# n64cart-v2-soic-8.net
KiCad netlist of a schematic drawn in EAGLE
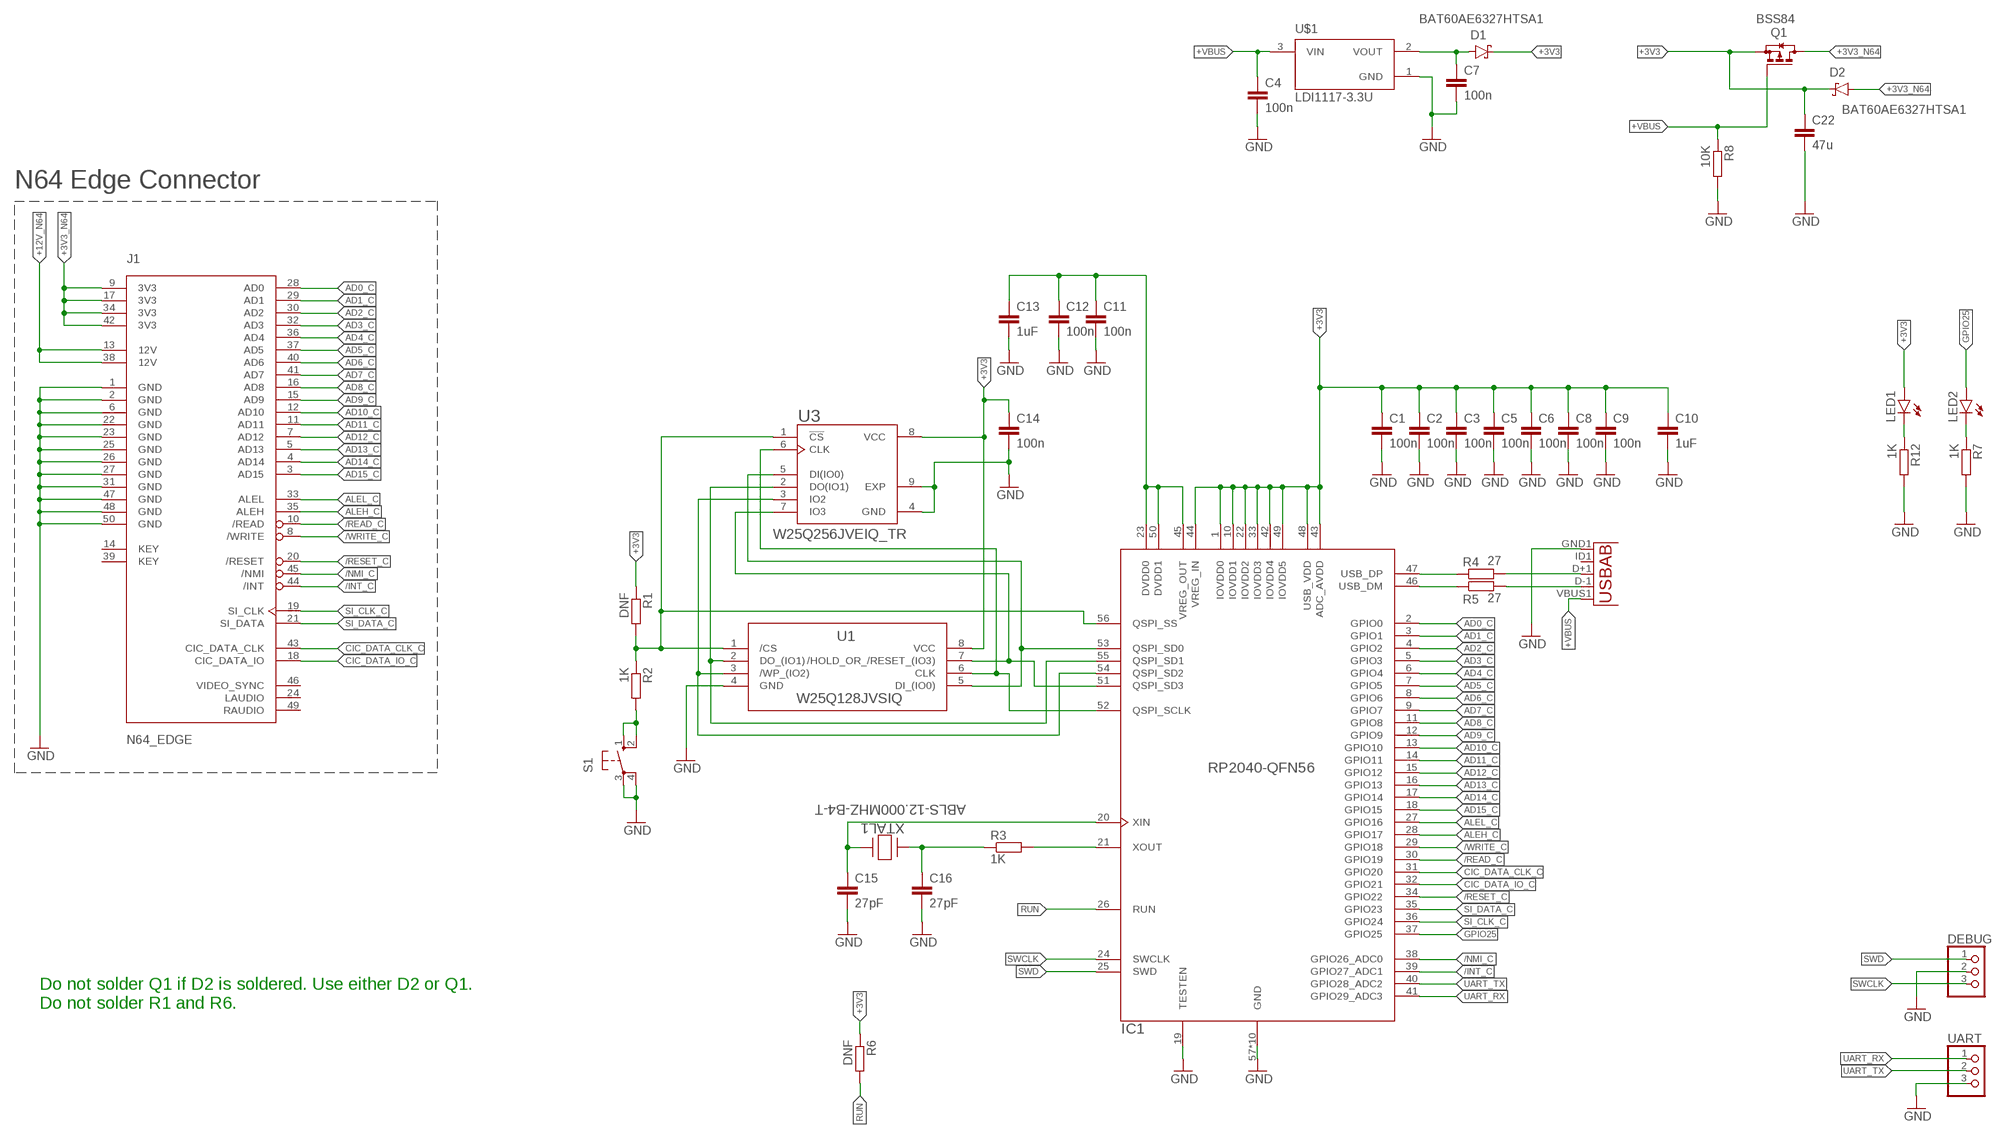
[diagram p0: schematic, sheet 1]

(export (version "E")
  (design (tool "Eeschema 10.0.6"))
  (components
    (comp (ref "C1")
      (value "100n")
      (footprint "eagle-import:C0402")
      (libsource (lib "eagle-import") (part "C-EUC0402"))
    )
    (comp (ref "C2")
      (value "100n")
      (footprint "eagle-import:C0402")
      (libsource (lib "eagle-import") (part "C-EUC0402"))
    )
    (comp (ref "C3")
      (value "100n")
      (footprint "eagle-import:C0402")
      (libsource (lib "eagle-import") (part "C-EUC0402"))
    )
    (comp (ref "C4")
      (value "100n")
      (footprint "eagle-import:C0402")
      (libsource (lib "eagle-import") (part "C-EUC0402"))
    )
    (comp (ref "C5")
      (value "100n")
      (footprint "eagle-import:C0402")
      (libsource (lib "eagle-import") (part "C-EUC0402"))
    )
    (comp (ref "C6")
      (value "100n")
      (footprint "eagle-import:C0402")
      (libsource (lib "eagle-import") (part "C-EUC0402"))
    )
    (comp (ref "C7")
      (value "100n")
      (footprint "eagle-import:C0402")
      (libsource (lib "eagle-import") (part "C-EUC0402"))
    )
    (comp (ref "C8")
      (value "100n")
      (footprint "eagle-import:C0402")
      (libsource (lib "eagle-import") (part "C-EUC0402"))
    )
    (comp (ref "C9")
      (value "100n")
      (footprint "eagle-import:C0402")
      (libsource (lib "eagle-import") (part "C-EUC0402"))
    )
    (comp (ref "C10")
      (value "1uF")
      (footprint "eagle-import:C0402")
      (libsource (lib "eagle-import") (part "C-EUC0402"))
    )
    (comp (ref "C11")
      (value "100n")
      (footprint "eagle-import:C0402")
      (libsource (lib "eagle-import") (part "C-EUC0402"))
    )
    (comp (ref "C12")
      (value "100n")
      (footprint "eagle-import:C0402")
      (libsource (lib "eagle-import") (part "C-EUC0402"))
    )
    (comp (ref "C13")
      (value "1uF")
      (footprint "eagle-import:C0402")
      (libsource (lib "eagle-import") (part "C-EUC0402"))
    )
    (comp (ref "C14")
      (value "100n")
      (footprint "eagle-import:C0402")
      (libsource (lib "eagle-import") (part "C-EUC0402"))
    )
    (comp (ref "C15")
      (value "27pF")
      (footprint "eagle-import:C0402")
      (libsource (lib "eagle-import") (part "C-EUC0402"))
    )
    (comp (ref "C16")
      (value "27pF")
      (footprint "eagle-import:C0402")
      (libsource (lib "eagle-import") (part "C-EUC0402"))
    )
    (comp (ref "C22")
      (value "47u")
      (footprint "eagle-import:C0805")
      (libsource (lib "eagle-import") (part "C-EUC0805"))
    )
    (comp (ref "D1")
      (value "BAT60AE6327HTSA1")
      (footprint "eagle-import:SOD323_ST")
      (libsource (lib "eagle-import") (part "BAT60J"))
    )
    (comp (ref "D2")
      (value "BAT60AE6327HTSA1")
      (footprint "eagle-import:SOD323_ST")
      (libsource (lib "eagle-import") (part "BAT60J"))
    )
    (comp (ref "DEBUG")
      (value "PINHD-1X3")
      (footprint "eagle-import:1X03")
      (libsource (lib "eagle-import") (part "PINHD-1X3"))
    )
    (comp (ref "IC1")
      (value "RP2040-QFN56")
      (footprint "eagle-import:RP2040-QFN-56")
      (libsource (lib "eagle-import") (part "RP2040-QFN56"))
    )
    (comp (ref "J1")
      (value "N64_EDGE")
      (footprint "eagle-import:N64_EDGE")
      (libsource (lib "eagle-import") (part "N64_EDGE"))
    )
    (comp (ref "LED1")
      (value "LED5MM")
      (footprint "eagle-import:LED5MM")
      (libsource (lib "eagle-import") (part "LED5MM"))
    )
    (comp (ref "LED2")
      (value "LED5MM")
      (footprint "eagle-import:LED5MM")
      (libsource (lib "eagle-import") (part "LED5MM"))
    )
    (comp (ref "Q1")
      (value "BSS84")
      (footprint "eagle-import:SOT23")
      (libsource (lib "eagle-import") (part "BSS84"))
    )
    (comp (ref "R1")
      (value "DNF")
      (footprint "eagle-import:R0402")
      (libsource (lib "eagle-import") (part "R-EU_R0402"))
    )
    (comp (ref "R2")
      (value "1K")
      (footprint "eagle-import:R0402")
      (libsource (lib "eagle-import") (part "R-EU_R0402"))
    )
    (comp (ref "R3")
      (value "1K")
      (footprint "eagle-import:R0402")
      (libsource (lib "eagle-import") (part "R-EU_R0402"))
    )
    (comp (ref "R4")
      (value "27")
      (footprint "eagle-import:R0402")
      (libsource (lib "eagle-import") (part "R-EU_R0402"))
    )
    (comp (ref "R5")
      (value "27")
      (footprint "eagle-import:R0402")
      (libsource (lib "eagle-import") (part "R-EU_R0402"))
    )
    (comp (ref "R6")
      (value "DNF")
      (footprint "eagle-import:R0402")
      (libsource (lib "eagle-import") (part "R-EU_R0402"))
    )
    (comp (ref "R7")
      (value "1K")
      (footprint "eagle-import:R0402")
      (libsource (lib "eagle-import") (part "R-EU_R0402"))
    )
    (comp (ref "R8")
      (value "10K")
      (footprint "eagle-import:R0402")
      (libsource (lib "eagle-import") (part "R-EU_R0402"))
    )
    (comp (ref "R12")
      (value "1K")
      (footprint "eagle-import:R0402")
      (libsource (lib "eagle-import") (part "R-EU_R0402"))
    )
    (comp (ref "S1")
      (value "10-XX")
      (footprint "eagle-import:B3F-10XX")
      (fields (field (name "MPN") "B3F-1000"))
      (libsource (lib "eagle-import") (part "10-XX"))
    )
    (comp (ref "U$1")
      (value "LDI1117-3.3U")
      (footprint "eagle-import:LDI1117-3.3U")
      (libsource (lib "eagle-import") (part "LDI1117-3.3U"))
    )
    (comp (ref "U1")
      (value "W25Q128JVSIQ")
      (footprint "eagle-import:SOIC_128JVSIQ_WIN")
      (fields (field (name "COPYRIGHT") "Copyright (C) 2022 Ultra Librarian. All rights reserved."))
      (libsource (lib "eagle-import") (part "W25Q128JVSIQ"))
    )
    (comp (ref "U2")
      (value "USB\"\"")
      (footprint "eagle-import:USB-MICRO-SMD")
      (libsource (lib "eagle-import") (part "USB{dblquote}{dblquote}"))
    )
    (comp (ref "U3")
      (value "W25Q256JVEIQ_TR")
      (footprint "eagle-import:SON127P800X600X80-9N")
      (fields
        (field (name "DIGI-KEY_PART_NUMBER") "W25Q256JVEIQTR-ND")
        (field (name "MF") "Winbond")
        (field (name "MP") "W25Q256JVEIQ TR")
      )
      (libsource (lib "eagle-import") (part "W25Q256JVEIQ_TR"))
    )
    (comp (ref "UART")
      (value "PINHD-1X3")
      (footprint "eagle-import:1X03")
      (libsource (lib "eagle-import") (part "PINHD-1X3"))
    )
    (comp (ref "XTAL1")
      (value "ABLS-12.000MHZ-B4-T")
      (footprint "eagle-import:XTAL_ABLS_ABR")
      (fields (field (name "COPYRIGHT") "Copyright (C) 2022 Ultra Librarian. All rights reserved."))
      (libsource (lib "eagle-import") (part "ABLS-12.000MHZ-B4-T"))
    )
  )
  (nets
    (net (code "1") (name "+3V3") (class "Default")
      (node (ref "C1") (pin "1") (pinfunction "1_1") (pintype "passive"))
      (node (ref "C10") (pin "1") (pinfunction "1_1") (pintype "passive"))
      (node (ref "C14") (pin "1") (pinfunction "1_1") (pintype "passive"))
      (node (ref "C2") (pin "1") (pinfunction "1_1") (pintype "passive"))
      (node (ref "C22") (pin "1") (pinfunction "1_1") (pintype "passive"))
      (node (ref "C3") (pin "1") (pinfunction "1_1") (pintype "passive"))
      (node (ref "C5") (pin "1") (pinfunction "1_1") (pintype "passive"))
      (node (ref "C6") (pin "1") (pinfunction "1_1") (pintype "passive"))
      (node (ref "C8") (pin "1") (pinfunction "1_1") (pintype "passive"))
      (node (ref "C9") (pin "1") (pinfunction "1_1") (pintype "passive"))
      (node (ref "D1") (pin "C") (pinfunction "C_C") (pintype "passive"))
      (node (ref "D2") (pin "C") (pinfunction "C_C") (pintype "passive"))
      (node (ref "IC1") (pin "1") (pinfunction "IOVDD0_1") (pintype "power_in"))
      (node (ref "IC1") (pin "10") (pinfunction "IOVDD1_10") (pintype "power_in"))
      (node (ref "IC1") (pin "22") (pinfunction "IOVDD2_22") (pintype "power_in"))
      (node (ref "IC1") (pin "33") (pinfunction "IOVDD3_33") (pintype "power_in"))
      (node (ref "IC1") (pin "42") (pinfunction "IOVDD4_42") (pintype "power_in"))
      (node (ref "IC1") (pin "43") (pinfunction "ADC_AVDD_43") (pintype "power_in"))
      (node (ref "IC1") (pin "44") (pinfunction "VREG_IN_44") (pintype "power_in"))
      (node (ref "IC1") (pin "48") (pinfunction "USB_VDD_48") (pintype "power_in"))
      (node (ref "IC1") (pin "49") (pinfunction "IOVDD5_49") (pintype "power_in"))
      (node (ref "LED1") (pin "A") (pinfunction "A_A") (pintype "passive"))
      (node (ref "Q1") (pin "2") (pinfunction "S_2") (pintype "passive"))
      (node (ref "R1") (pin "1") (pinfunction "1_1") (pintype "passive"))
      (node (ref "R6") (pin "1") (pinfunction "1_1") (pintype "passive"))
      (node (ref "U1") (pin "8") (pinfunction "VCC_8") (pintype "power_in"))
      (node (ref "U3") (pin "8") (pinfunction "VCC_8") (pintype "power_in"))
    )
    (net (code "2") (name "+3V3_N64") (class "Default")
      (node (ref "D2") (pin "A") (pinfunction "A_A") (pintype "passive"))
      (node (ref "J1") (pin "17") (pinfunction "3V3_17") (pintype "power_in"))
      (node (ref "J1") (pin "34") (pinfunction "3V3_34") (pintype "power_in"))
      (node (ref "J1") (pin "42") (pinfunction "3V3_42") (pintype "power_in"))
      (node (ref "J1") (pin "9") (pinfunction "3V3_9") (pintype "power_in"))
      (node (ref "Q1") (pin "3") (pinfunction "D_3") (pintype "passive"))
    )
    (net (code "3") (name "+12V_N64") (class "Default")
      (node (ref "J1") (pin "13") (pinfunction "12V_13") (pintype "power_in"))
      (node (ref "J1") (pin "38") (pinfunction "12V_38") (pintype "power_in"))
    )
    (net (code "4") (name "+VBUS") (class "Default")
      (node (ref "C4") (pin "1") (pinfunction "1_1") (pintype "passive"))
      (node (ref "Q1") (pin "1") (pinfunction "G_1") (pintype "passive"))
      (node (ref "R8") (pin "1") (pinfunction "1_1") (pintype "passive"))
      (node (ref "U$1") (pin "3") (pinfunction "VIN_3") (pintype "input"))
      (node (ref "U2") (pin "VBUS1") (pinfunction "VBUS_VBUS1") (pintype "bidirectional"))
    )
    (net (code "5") (name "AD0_C") (class "Default")
      (node (ref "IC1") (pin "2") (pinfunction "GPIO0_2") (pintype "bidirectional"))
      (node (ref "J1") (pin "28") (pinfunction "AD0_28") (pintype "bidirectional"))
    )
    (net (code "6") (name "AD1_C") (class "Default")
      (node (ref "IC1") (pin "3") (pinfunction "GPIO1_3") (pintype "bidirectional"))
      (node (ref "J1") (pin "29") (pinfunction "AD1_29") (pintype "bidirectional"))
    )
    (net (code "7") (name "AD2_C") (class "Default")
      (node (ref "IC1") (pin "4") (pinfunction "GPIO2_4") (pintype "bidirectional"))
      (node (ref "J1") (pin "30") (pinfunction "AD2_30") (pintype "bidirectional"))
    )
    (net (code "8") (name "AD3_C") (class "Default")
      (node (ref "IC1") (pin "5") (pinfunction "GPIO3_5") (pintype "bidirectional"))
      (node (ref "J1") (pin "32") (pinfunction "AD3_32") (pintype "bidirectional"))
    )
    (net (code "9") (name "AD4_C") (class "Default")
      (node (ref "IC1") (pin "6") (pinfunction "GPIO4_6") (pintype "bidirectional"))
      (node (ref "J1") (pin "36") (pinfunction "AD4_36") (pintype "bidirectional"))
    )
    (net (code "10") (name "AD5_C") (class "Default")
      (node (ref "IC1") (pin "7") (pinfunction "GPIO5_7") (pintype "bidirectional"))
      (node (ref "J1") (pin "37") (pinfunction "AD5_37") (pintype "bidirectional"))
    )
    (net (code "11") (name "AD6_C") (class "Default")
      (node (ref "IC1") (pin "8") (pinfunction "GPIO6_8") (pintype "bidirectional"))
      (node (ref "J1") (pin "40") (pinfunction "AD6_40") (pintype "bidirectional"))
    )
    (net (code "12") (name "AD7_C") (class "Default")
      (node (ref "IC1") (pin "9") (pinfunction "GPIO7_9") (pintype "bidirectional"))
      (node (ref "J1") (pin "41") (pinfunction "AD7_41") (pintype "bidirectional"))
    )
    (net (code "13") (name "AD8_C") (class "Default")
      (node (ref "IC1") (pin "11") (pinfunction "GPIO8_11") (pintype "bidirectional"))
      (node (ref "J1") (pin "16") (pinfunction "AD8_16") (pintype "bidirectional"))
    )
    (net (code "14") (name "AD9_C") (class "Default")
      (node (ref "IC1") (pin "12") (pinfunction "GPIO9_12") (pintype "bidirectional"))
      (node (ref "J1") (pin "15") (pinfunction "AD9_15") (pintype "bidirectional"))
    )
    (net (code "15") (name "AD10_C") (class "Default")
      (node (ref "IC1") (pin "13") (pinfunction "GPIO10_13") (pintype "bidirectional"))
      (node (ref "J1") (pin "12") (pinfunction "AD10_12") (pintype "bidirectional"))
    )
    (net (code "16") (name "AD11_C") (class "Default")
      (node (ref "IC1") (pin "14") (pinfunction "GPIO11_14") (pintype "bidirectional"))
      (node (ref "J1") (pin "11") (pinfunction "AD11_11") (pintype "bidirectional"))
    )
    (net (code "17") (name "AD12_C") (class "Default")
      (node (ref "IC1") (pin "15") (pinfunction "GPIO12_15") (pintype "bidirectional"))
      (node (ref "J1") (pin "7") (pinfunction "AD12_7") (pintype "bidirectional"))
    )
    (net (code "18") (name "AD13_C") (class "Default")
      (node (ref "IC1") (pin "16") (pinfunction "GPIO13_16") (pintype "bidirectional"))
      (node (ref "J1") (pin "5") (pinfunction "AD13_5") (pintype "bidirectional"))
    )
    (net (code "19") (name "AD14_C") (class "Default")
      (node (ref "IC1") (pin "17") (pinfunction "GPIO14_17") (pintype "bidirectional"))
      (node (ref "J1") (pin "4") (pinfunction "AD14_4") (pintype "bidirectional"))
    )
    (net (code "20") (name "AD15_C") (class "Default")
      (node (ref "IC1") (pin "18") (pinfunction "GPIO15_18") (pintype "bidirectional"))
      (node (ref "J1") (pin "3") (pinfunction "AD15_3") (pintype "bidirectional"))
    )
    (net (code "21") (name "ALEH_C") (class "Default")
      (node (ref "IC1") (pin "28") (pinfunction "GPIO17_28") (pintype "bidirectional"))
      (node (ref "J1") (pin "35") (pinfunction "ALEH_35") (pintype "output"))
    )
    (net (code "22") (name "ALEL_C") (class "Default")
      (node (ref "IC1") (pin "27") (pinfunction "GPIO16_27") (pintype "bidirectional"))
      (node (ref "J1") (pin "33") (pinfunction "ALEL_33") (pintype "output"))
    )
    (net (code "23") (name "CIC_DATA_CLK_C") (class "Default")
      (node (ref "IC1") (pin "31") (pinfunction "GPIO20_31") (pintype "bidirectional"))
      (node (ref "J1") (pin "43") (pinfunction "CIC_DATA_CLK_43") (pintype "output"))
    )
    (net (code "24") (name "CIC_DATA_IO_C") (class "Default")
      (node (ref "IC1") (pin "32") (pinfunction "GPIO21_32") (pintype "bidirectional"))
      (node (ref "J1") (pin "18") (pinfunction "CIC_DATA_IO_18") (pintype "bidirectional"))
    )
    (net (code "25") (name "GND") (class "Default")
      (node (ref "C1") (pin "2") (pinfunction "2_2") (pintype "passive"))
      (node (ref "C10") (pin "2") (pinfunction "2_2") (pintype "passive"))
      (node (ref "C11") (pin "2") (pinfunction "2_2") (pintype "passive"))
      (node (ref "C12") (pin "2") (pinfunction "2_2") (pintype "passive"))
      (node (ref "C13") (pin "2") (pinfunction "2_2") (pintype "passive"))
      (node (ref "C14") (pin "2") (pinfunction "2_2") (pintype "passive"))
      (node (ref "C15") (pin "2") (pinfunction "2_2") (pintype "passive"))
      (node (ref "C16") (pin "2") (pinfunction "2_2") (pintype "passive"))
      (node (ref "C2") (pin "2") (pinfunction "2_2") (pintype "passive"))
      (node (ref "C22") (pin "2") (pinfunction "2_2") (pintype "passive"))
      (node (ref "C3") (pin "2") (pinfunction "2_2") (pintype "passive"))
      (node (ref "C4") (pin "2") (pinfunction "2_2") (pintype "passive"))
      (node (ref "C5") (pin "2") (pinfunction "2_2") (pintype "passive"))
      (node (ref "C6") (pin "2") (pinfunction "2_2") (pintype "passive"))
      (node (ref "C7") (pin "2") (pinfunction "2_2") (pintype "passive"))
      (node (ref "C8") (pin "2") (pinfunction "2_2") (pintype "passive"))
      (node (ref "C9") (pin "2") (pinfunction "2_2") (pintype "passive"))
      (node (ref "DEBUG") (pin "2") (pinfunction "2_2") (pintype "passive"))
      (node (ref "IC1") (pin "19") (pinfunction "TESTEN_19") (pintype "passive"))
      (node (ref "IC1") (pin "57") (pinfunction "GND_57") (pintype "power_in"))
      (node (ref "IC1") (pin "58") (pinfunction "GND_58") (pintype "power_in"))
      (node (ref "IC1") (pin "59") (pinfunction "GND_59") (pintype "power_in"))
      (node (ref "IC1") (pin "60") (pinfunction "GND_60") (pintype "power_in"))
      (node (ref "IC1") (pin "61") (pinfunction "GND_61") (pintype "power_in"))
      (node (ref "IC1") (pin "62") (pinfunction "GND_62") (pintype "power_in"))
      (node (ref "IC1") (pin "63") (pinfunction "GND_63") (pintype "power_in"))
      (node (ref "IC1") (pin "64") (pinfunction "GND_64") (pintype "power_in"))
      (node (ref "IC1") (pin "65") (pinfunction "GND_65") (pintype "power_in"))
      (node (ref "IC1") (pin "66") (pinfunction "GND_66") (pintype "power_in"))
      (node (ref "J1") (pin "1") (pinfunction "GND_1") (pintype "power_in"))
      (node (ref "J1") (pin "2") (pinfunction "GND_2") (pintype "power_in"))
      (node (ref "J1") (pin "22") (pinfunction "GND_22") (pintype "power_in"))
      (node (ref "J1") (pin "23") (pinfunction "GND_23") (pintype "power_in"))
      (node (ref "J1") (pin "25") (pinfunction "GND_25") (pintype "power_in"))
      (node (ref "J1") (pin "26") (pinfunction "GND_26") (pintype "power_in"))
      (node (ref "J1") (pin "27") (pinfunction "GND_27") (pintype "power_in"))
      (node (ref "J1") (pin "31") (pinfunction "GND_31") (pintype "power_in"))
      (node (ref "J1") (pin "47") (pinfunction "GND_47") (pintype "power_in"))
      (node (ref "J1") (pin "48") (pinfunction "GND_48") (pintype "power_in"))
      (node (ref "J1") (pin "50") (pinfunction "GND_50") (pintype "power_in"))
      (node (ref "J1") (pin "6") (pinfunction "GND_6") (pintype "power_in"))
      (node (ref "R12") (pin "2") (pinfunction "2_2") (pintype "passive"))
      (node (ref "R7") (pin "2") (pinfunction "2_2") (pintype "passive"))
      (node (ref "R8") (pin "2") (pinfunction "2_2") (pintype "passive"))
      (node (ref "S1") (pin "3") (pinfunction "P_3") (pintype "passive"))
      (node (ref "S1") (pin "4") (pinfunction "P1_4") (pintype "passive"))
      (node (ref "U$1") (pin "1") (pinfunction "GND_1") (pintype "power_in"))
      (node (ref "U1") (pin "4") (pinfunction "GND_4") (pintype "passive"))
      (node (ref "U2") (pin "GND1") (pinfunction "GND_GND1") (pintype "bidirectional"))
      (node (ref "U3") (pin "4") (pinfunction "GND_4") (pintype "power_in"))
      (node (ref "U3") (pin "9") (pinfunction "EXP_9") (pintype "power_in"))
      (node (ref "UART") (pin "3") (pinfunction "3_3") (pintype "passive"))
    )
    (net (code "26") (name "GPIO25") (class "Default")
      (node (ref "IC1") (pin "37") (pinfunction "GPIO25_37") (pintype "bidirectional"))
      (node (ref "LED2") (pin "A") (pinfunction "A_A") (pintype "passive"))
    )
    (net (code "27") (name "Net-(C16-Pad1)") (class "Default")
      (node (ref "C16") (pin "1") (pinfunction "1_1") (pintype "passive"))
      (node (ref "R3") (pin "1") (pinfunction "1_1") (pintype "passive"))
      (node (ref "XTAL1") (pin "1") (pinfunction "1_1") (pintype "passive"))
    )
    (net (code "28") (name "Net-(IC1-DVDD0)") (class "Default")
      (node (ref "C11") (pin "1") (pinfunction "1_1") (pintype "passive"))
      (node (ref "C12") (pin "1") (pinfunction "1_1") (pintype "passive"))
      (node (ref "C13") (pin "1") (pinfunction "1_1") (pintype "passive"))
      (node (ref "IC1") (pin "23") (pinfunction "DVDD0_23") (pintype "power_in"))
      (node (ref "IC1") (pin "45") (pinfunction "VREG_OUT_45") (pintype "power_in"))
      (node (ref "IC1") (pin "50") (pinfunction "DVDD1_50") (pintype "power_in"))
    )
    (net (code "29") (name "Net-(IC1-QSPI_SCLK)") (class "Default")
      (node (ref "IC1") (pin "52") (pinfunction "QSPI_SCLK_52") (pintype "output"))
      (node (ref "U1") (pin "6") (pinfunction "CLK_6") (pintype "passive"))
      (node (ref "U3") (pin "6") (pinfunction "CLK_6") (pintype "input"))
    )
    (net (code "30") (name "Net-(IC1-QSPI_SD0)") (class "Default")
      (node (ref "IC1") (pin "53") (pinfunction "QSPI_SD0_53") (pintype "bidirectional"))
      (node (ref "U1") (pin "5") (pinfunction "DI_(IO0)_5") (pintype "passive"))
      (node (ref "U3") (pin "5") (pinfunction "DI(IO0)_5") (pintype "bidirectional"))
    )
    (net (code "31") (name "Net-(IC1-QSPI_SD1)") (class "Default")
      (node (ref "IC1") (pin "55") (pinfunction "QSPI_SD1_55") (pintype "bidirectional"))
      (node (ref "U1") (pin "2") (pinfunction "DO_(IO1)_2") (pintype "passive"))
      (node (ref "U3") (pin "2") (pinfunction "DO(IO1)_2") (pintype "bidirectional"))
    )
    (net (code "32") (name "Net-(IC1-QSPI_SD2)") (class "Default")
      (node (ref "IC1") (pin "54") (pinfunction "QSPI_SD2_54") (pintype "bidirectional"))
      (node (ref "U1") (pin "3") (pinfunction "/WP_(IO2)_3") (pintype "passive"))
      (node (ref "U3") (pin "3") (pinfunction "IO2_3") (pintype "bidirectional"))
    )
    (net (code "33") (name "Net-(IC1-QSPI_SD3)") (class "Default")
      (node (ref "IC1") (pin "51") (pinfunction "QSPI_SD3_51") (pintype "bidirectional"))
      (node (ref "U1") (pin "7") (pinfunction "/HOLD_OR_/RESET_(IO3)_7") (pintype "passive"))
      (node (ref "U3") (pin "7") (pinfunction "IO3_7") (pintype "bidirectional"))
    )
    (net (code "34") (name "Net-(IC1-QSPI_SS)") (class "Default")
      (node (ref "IC1") (pin "56") (pinfunction "QSPI_SS_56") (pintype "bidirectional"))
      (node (ref "R1") (pin "2") (pinfunction "2_2") (pintype "passive"))
      (node (ref "R2") (pin "1") (pinfunction "1_1") (pintype "passive"))
      (node (ref "U1") (pin "1") (pinfunction "/CS_1") (pintype "passive"))
      (node (ref "U3") (pin "1") (pinfunction "~{CS}_1") (pintype "input"))
    )
    (net (code "35") (name "Net-(IC1-USB_DM)") (class "Default")
      (node (ref "IC1") (pin "46") (pinfunction "USB_DM_46") (pintype "bidirectional"))
      (node (ref "R5") (pin "1") (pinfunction "1_1") (pintype "passive"))
    )
    (net (code "36") (name "Net-(IC1-USB_DP)") (class "Default")
      (node (ref "IC1") (pin "47") (pinfunction "USB_DP_47") (pintype "bidirectional"))
      (node (ref "R4") (pin "1") (pinfunction "1_1") (pintype "passive"))
    )
    (net (code "37") (name "Net-(IC1-XIN)") (class "Default")
      (node (ref "C15") (pin "1") (pinfunction "1_1") (pintype "passive"))
      (node (ref "IC1") (pin "20") (pinfunction "XIN_20") (pintype "input"))
      (node (ref "XTAL1") (pin "2") (pinfunction "2_2") (pintype "passive"))
    )
    (net (code "38") (name "Net-(IC1-XOUT)") (class "Default")
      (node (ref "IC1") (pin "21") (pinfunction "XOUT_21") (pintype "passive"))
      (node (ref "R3") (pin "2") (pinfunction "2_2") (pintype "passive"))
    )
    (net (code "39") (name "Net-(LED1-C)") (class "Default")
      (node (ref "LED1") (pin "K") (pinfunction "C_K") (pintype "passive"))
      (node (ref "R12") (pin "1") (pinfunction "1_1") (pintype "passive"))
    )
    (net (code "40") (name "Net-(LED2-C)") (class "Default")
      (node (ref "LED2") (pin "K") (pinfunction "C_K") (pintype "passive"))
      (node (ref "R7") (pin "1") (pinfunction "1_1") (pintype "passive"))
    )
    (net (code "41") (name "Net-(S1-S)") (class "Default")
      (node (ref "R2") (pin "2") (pinfunction "2_2") (pintype "passive"))
      (node (ref "S1") (pin "1") (pinfunction "S_1") (pintype "passive"))
      (node (ref "S1") (pin "2") (pinfunction "S1_2") (pintype "passive"))
    )
    (net (code "42") (name "Net-(U$1-VOUT)") (class "Default")
      (node (ref "C7") (pin "1") (pinfunction "1_1") (pintype "passive"))
      (node (ref "D1") (pin "A") (pinfunction "A_A") (pintype "passive"))
      (node (ref "U$1") (pin "2") (pinfunction "VOUT_2") (pintype "output"))
    )
    (net (code "43") (name "Net-(U2-D+)") (class "Default")
      (node (ref "R4") (pin "2") (pinfunction "2_2") (pintype "passive"))
      (node (ref "U2") (pin "D+1") (pinfunction "D+_D+1") (pintype "bidirectional"))
    )
    (net (code "44") (name "Net-(U2-D-)") (class "Default")
      (node (ref "R5") (pin "2") (pinfunction "2_2") (pintype "passive"))
      (node (ref "U2") (pin "D-1") (pinfunction "D-_D-1") (pintype "bidirectional"))
    )
    (net (code "45") (name "RUN") (class "Default")
      (node (ref "IC1") (pin "26") (pinfunction "RUN_26") (pintype "input"))
      (node (ref "R6") (pin "2") (pinfunction "2_2") (pintype "passive"))
    )
    (net (code "46") (name "SI_CLK_C") (class "Default")
      (node (ref "IC1") (pin "36") (pinfunction "GPIO24_36") (pintype "bidirectional"))
      (node (ref "J1") (pin "19") (pinfunction "SI_CLK_19") (pintype "output"))
    )
    (net (code "47") (name "SI_DATA_C") (class "Default")
      (node (ref "IC1") (pin "35") (pinfunction "GPIO23_35") (pintype "bidirectional"))
      (node (ref "J1") (pin "21") (pinfunction "SI_DATA_21") (pintype "bidirectional"))
    )
    (net (code "48") (name "SWCLK") (class "Default")
      (node (ref "DEBUG") (pin "3") (pinfunction "3_3") (pintype "passive"))
      (node (ref "IC1") (pin "24") (pinfunction "SWCLK_24") (pintype "output"))
    )
    (net (code "49") (name "SWD") (class "Default")
      (node (ref "DEBUG") (pin "1") (pinfunction "1_1") (pintype "passive"))
      (node (ref "IC1") (pin "25") (pinfunction "SWD_25") (pintype "bidirectional"))
    )
    (net (code "50") (name "UART_RX") (class "Default")
      (node (ref "IC1") (pin "41") (pinfunction "GPIO29_ADC3_41") (pintype "bidirectional"))
      (node (ref "UART") (pin "1") (pinfunction "1_1") (pintype "passive"))
    )
    (net (code "51") (name "UART_TX") (class "Default")
      (node (ref "IC1") (pin "40") (pinfunction "GPIO28_ADC2_40") (pintype "bidirectional"))
      (node (ref "UART") (pin "2") (pinfunction "2_2") (pintype "passive"))
    )
    (net (code "52") (name "unconnected-(J1-KEY-Pad14)") (class "Default")
      (node (ref "J1") (pin "14") (pinfunction "KEY_14") (pintype "no_connect"))
    )
    (net (code "53") (name "unconnected-(J1-KEY-Pad39)") (class "Default")
      (node (ref "J1") (pin "39") (pinfunction "KEY_39") (pintype "no_connect"))
    )
    (net (code "54") (name "unconnected-(J1-LAUDIO-Pad24)") (class "Default")
      (node (ref "J1") (pin "24") (pinfunction "LAUDIO_24") (pintype "input"))
    )
    (net (code "55") (name "unconnected-(J1-RAUDIO-Pad49)") (class "Default")
      (node (ref "J1") (pin "49") (pinfunction "RAUDIO_49") (pintype "input"))
    )
    (net (code "56") (name "unconnected-(J1-VIDEO_SYNC-Pad46)") (class "Default")
      (node (ref "J1") (pin "46") (pinfunction "VIDEO_SYNC_46") (pintype "output"))
    )
    (net (code "57") (name "unconnected-(U2-USBID-PadID1)") (class "Default")
      (node (ref "U2") (pin "ID1") (pinfunction "USBID_ID1") (pintype "bidirectional"))
    )
    (net (code "58") (name "{slash}INT_C") (class "Default")
      (node (ref "IC1") (pin "39") (pinfunction "GPIO27_ADC1_39") (pintype "bidirectional"))
      (node (ref "J1") (pin "44") (pinfunction "/INT_44") (pintype "input"))
    )
    (net (code "59") (name "{slash}NMI_C") (class "Default")
      (node (ref "IC1") (pin "38") (pinfunction "GPIO26_ADC0_38") (pintype "bidirectional"))
      (node (ref "J1") (pin "45") (pinfunction "/NMI_45") (pintype "output"))
    )
    (net (code "60") (name "{slash}READ_C") (class "Default")
      (node (ref "IC1") (pin "30") (pinfunction "GPIO19_30") (pintype "bidirectional"))
      (node (ref "J1") (pin "10") (pinfunction "/READ_10") (pintype "output"))
    )
    (net (code "61") (name "{slash}RESET_C") (class "Default")
      (node (ref "IC1") (pin "34") (pinfunction "GPIO22_34") (pintype "bidirectional"))
      (node (ref "J1") (pin "20") (pinfunction "/RESET_20") (pintype "output"))
    )
    (net (code "62") (name "{slash}WRITE_C") (class "Default")
      (node (ref "IC1") (pin "29") (pinfunction "GPIO18_29") (pintype "bidirectional"))
      (node (ref "J1") (pin "8") (pinfunction "/WRITE_8") (pintype "output"))
    )
  )
)
